# schematic.net
KiCad netlist of a schematic drawn in EasyEDA
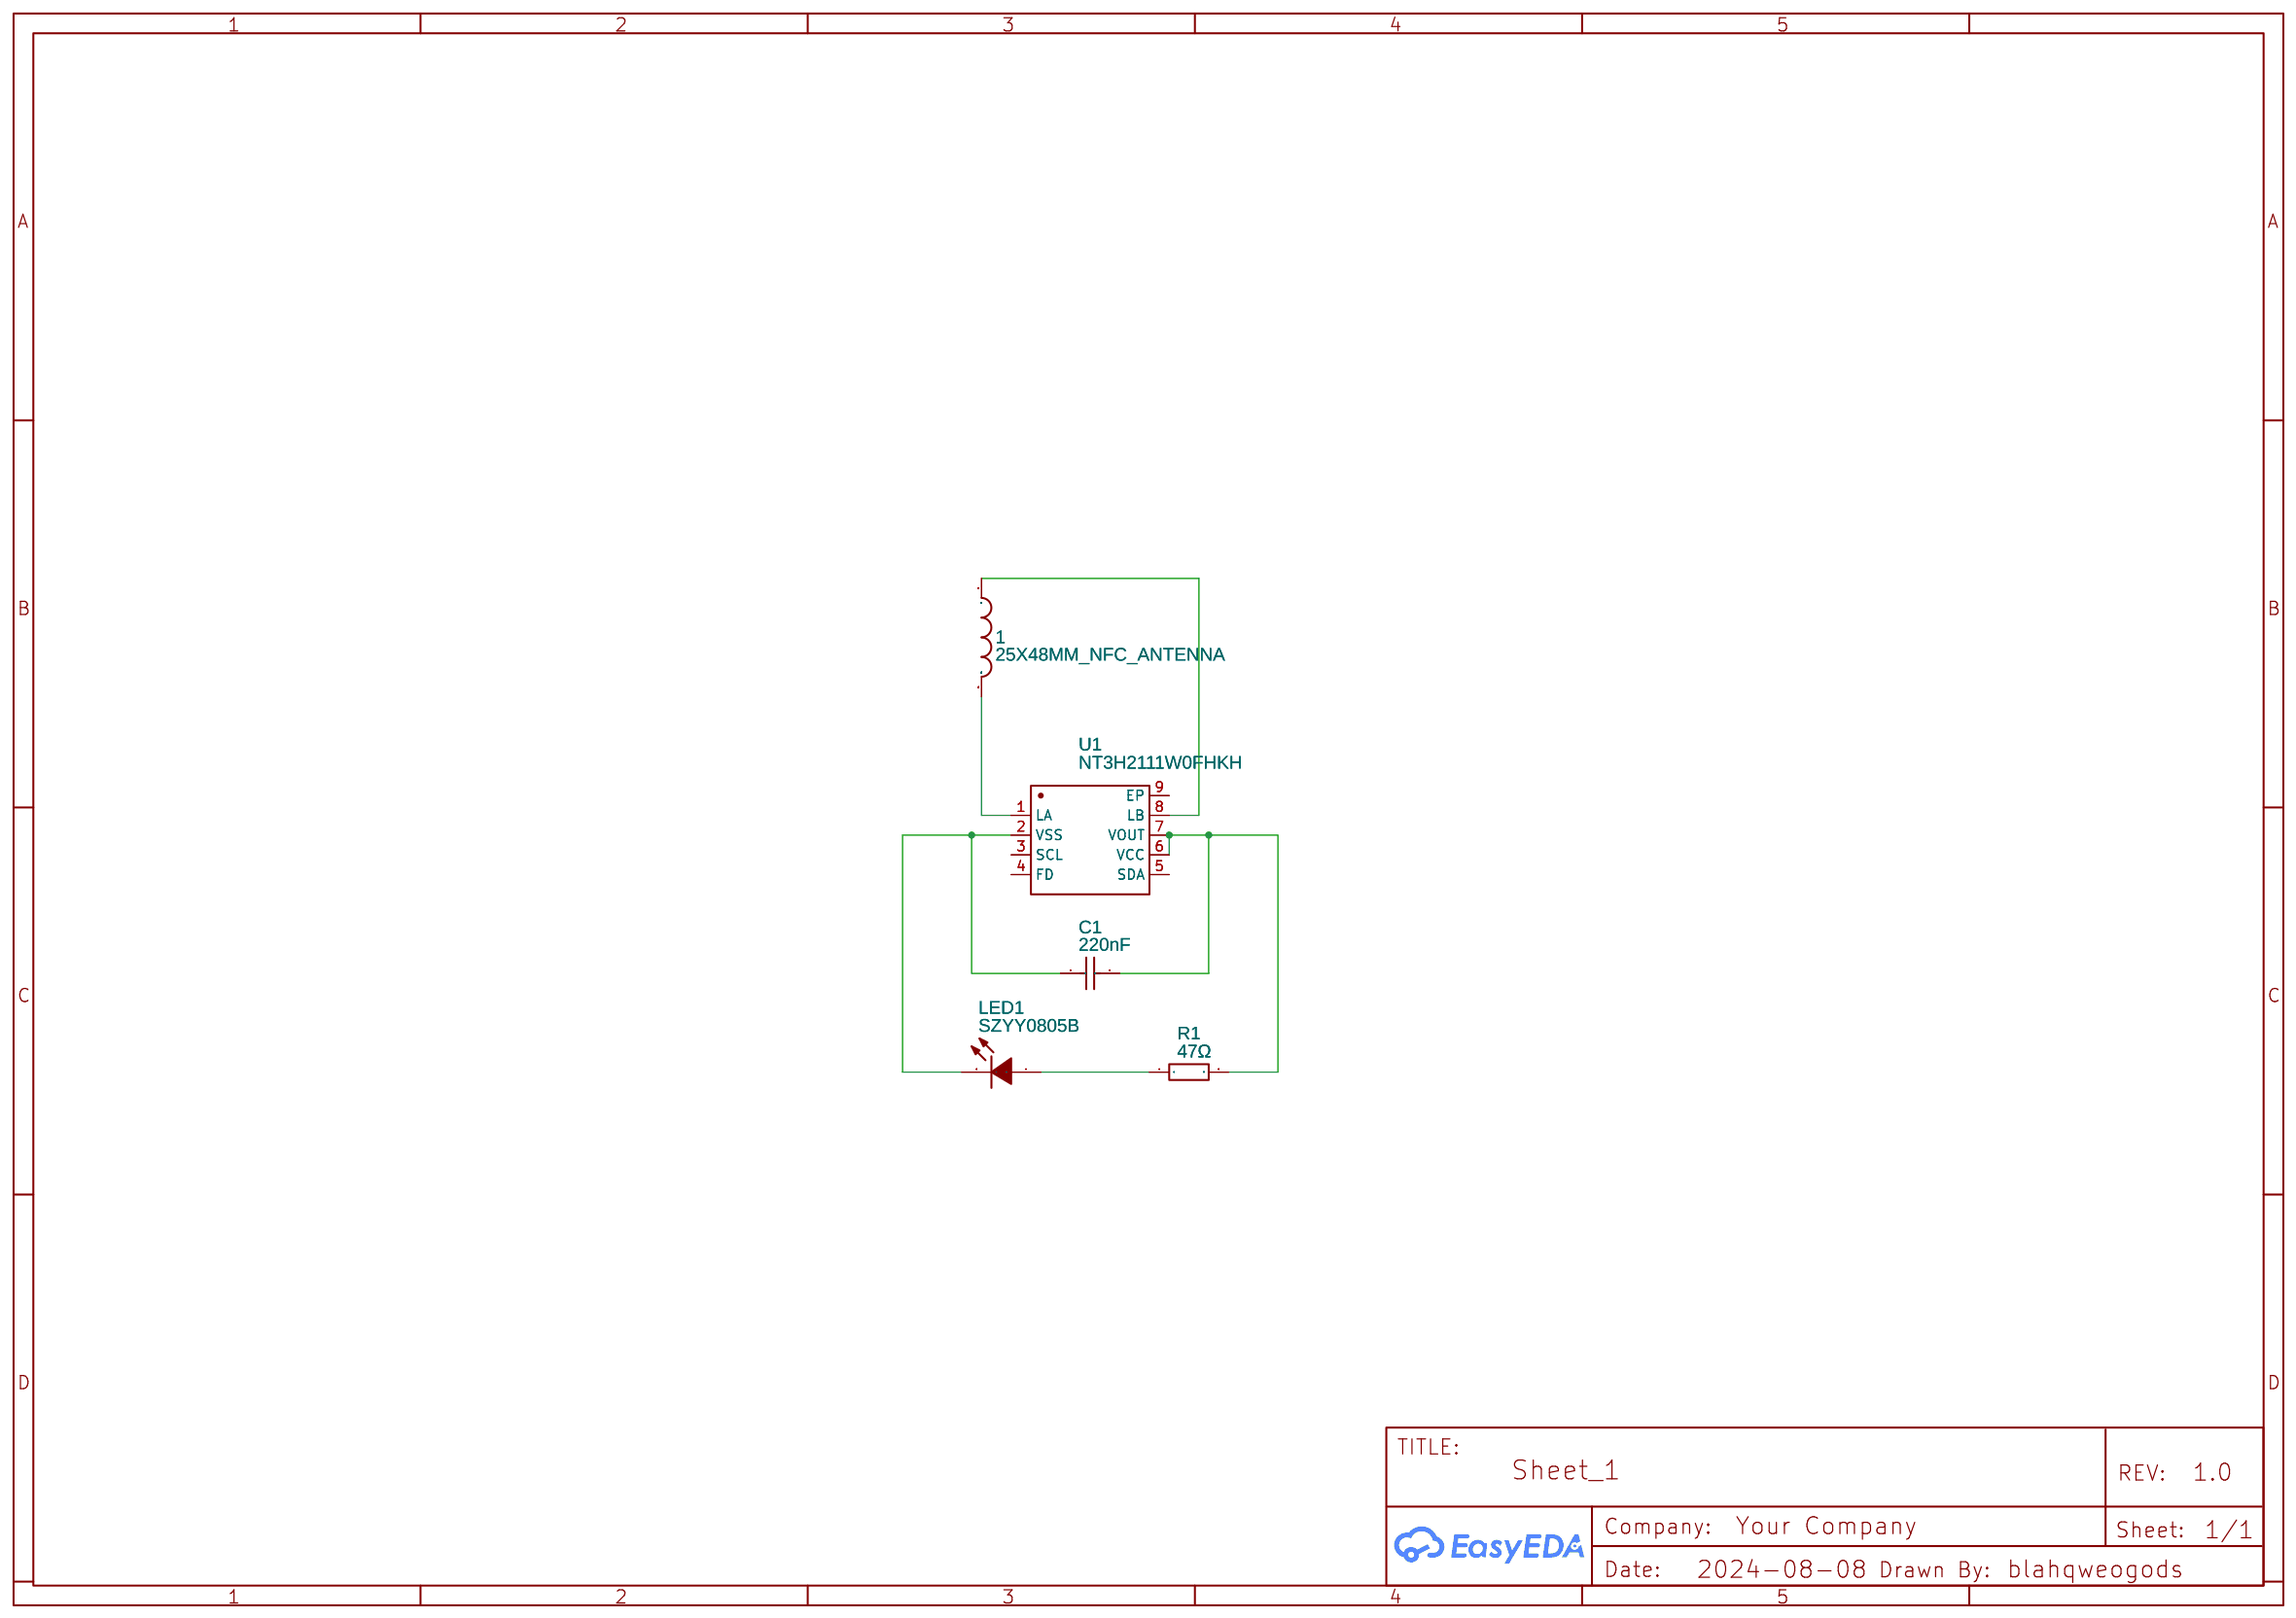
[diagram p0: schematic sheet]

(export (version "E")
  (design (tool "Eeschema 10.0.6"))
  (components
    (comp (ref "1") (value "25X48MM_NFC_ANTENNA") (libsource (lib "") (part "25X48MM_NFC_ANTENNA")))
    (comp (ref "C1")
      (value "220nF")
      (fields
        (field (name "Manufacturer Part") "CL10B224KA8NNNC")
        (field (name "Manufacturer") "SAMSUNG(三星)")
      )
      (libsource (lib "") (part "CL10B224KA8NNNC"))
    )
    (comp (ref "LED1")
      (value "SZYY0805B")
      (fields (field (name "Manufacturer") "yongyu(永裕光电)"))
      (libsource (lib "") (part "SZYY0805B"))
    )
    (comp (ref "R1")
      (value "47Ω")
      (fields
        (field (name "Manufacturer Part") "0603WAF470JT5E")
        (field (name "Manufacturer") "UNI-ROYAL(厚声)")
      )
      (libsource (lib "") (part "0603WAF470JT5E"))
    )
    (comp (ref "U1")
      (value "NT3H2111W0FHKH")
      (fields (field (name "Manufacturer") "NXP(恩智浦)"))
      (libsource (lib "") (part "NT3H2111W0FHKH"))
    )
  )
  (nets
    (net (code "1") (name "Net-(LED1-+)") (class "Default")
      (node (ref "LED1") (pin "1") (pinfunction "+_1") (pintype "unspecified"))
      (node (ref "R1") (pin "1") (pinfunction "1_1") (pintype "input"))
    )
    (net (code "2") (name "Net-(LED1--)") (class "Default")
      (node (ref "C1") (pin "1") (pinfunction "1_1") (pintype "input"))
      (node (ref "LED1") (pin "2") (pinfunction "-_2") (pintype "unspecified"))
      (node (ref "U1") (pin "2") (pinfunction "VSS_2") (pintype "unspecified"))
    )
    (net (code "3") (name "Net-(U1-LA)") (class "Default")
      (node (ref "1") (pin "P$2") (pinfunction "P$2_P$2") (pintype "bidirectional"))
      (node (ref "U1") (pin "1") (pinfunction "LA_1") (pintype "unspecified"))
    )
    (net (code "4") (name "Net-(U1-LB)") (class "Default")
      (node (ref "1") (pin "P$1") (pinfunction "P$1_P$1") (pintype "bidirectional"))
      (node (ref "U1") (pin "8") (pinfunction "LB_8") (pintype "unspecified"))
    )
    (net (code "5") (name "Net-(U1-VCC)") (class "Default")
      (node (ref "C1") (pin "2") (pinfunction "2_2") (pintype "input"))
      (node (ref "R1") (pin "2") (pinfunction "2_2") (pintype "input"))
      (node (ref "U1") (pin "6") (pinfunction "VCC_6") (pintype "unspecified"))
      (node (ref "U1") (pin "7") (pinfunction "VOUT_7") (pintype "unspecified"))
    )
    (net (code "6") (name "unconnected-(U1-EP-Pad9)") (class "Default")
      (node (ref "U1") (pin "9") (pinfunction "EP_9") (pintype "unspecified"))
    )
    (net (code "7") (name "unconnected-(U1-FD-Pad4)") (class "Default")
      (node (ref "U1") (pin "4") (pinfunction "FD_4") (pintype "unspecified"))
    )
    (net (code "8") (name "unconnected-(U1-SCL-Pad3)") (class "Default")
      (node (ref "U1") (pin "3") (pinfunction "SCL_3") (pintype "unspecified"))
    )
    (net (code "9") (name "unconnected-(U1-SDA-Pad5)") (class "Default")
      (node (ref "U1") (pin "5") (pinfunction "SDA_5") (pintype "unspecified"))
    )
  )
)
